# SUBBOARD-gate_driver.net
KiCad netlist of a schematic drawn in Altium Designer
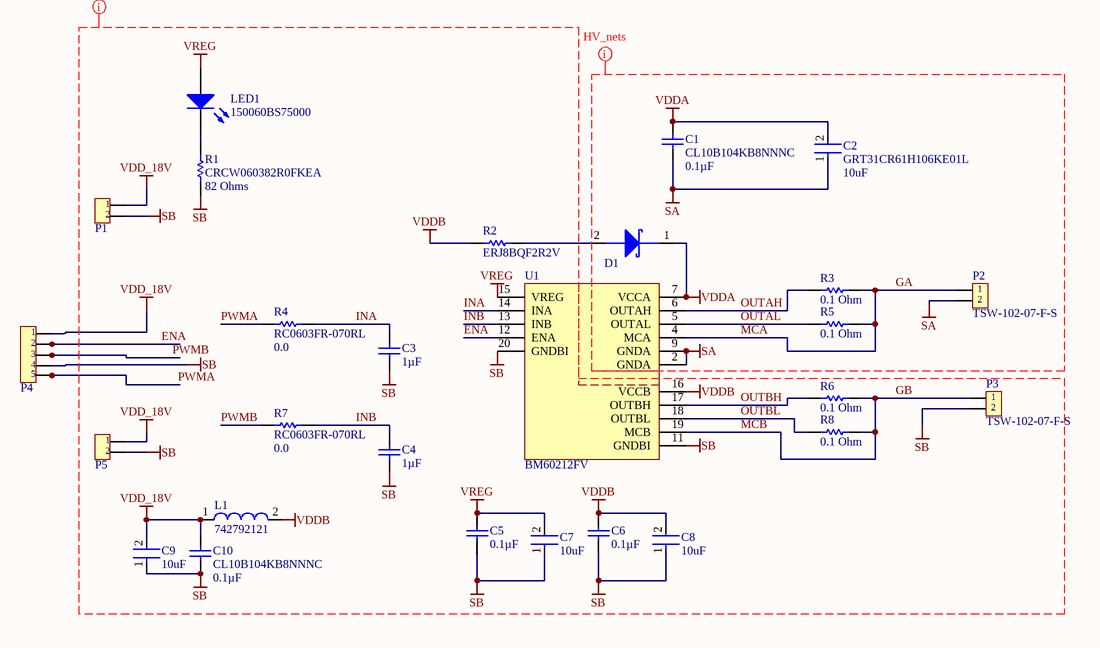
[diagram p0: SUBBOARD-gate_driver.SchDoc]

(export (version "E")
  (design (tool "Eeschema 10.0.6"))
  (components
    (comp (ref "C1")
      (value "CL10B104KB8NNNC")
      (footprint "SAMS-C0603-2_L")
      (description "Multi-layer Ceramic Capacitor, -55 to 125 degC, 2-Pin SMD (0603), RoHS, Tape and Reel")
      (fields (field (name "CAPACITANCE") "0.1µF") (field (name "MANUFACTURER") "Samsung Electro-Mechanics"))
      (libsource (lib "Altium Content Vault") (part "CAP-NP-2"))
    )
    (comp (ref "C2")
      (value "GRT31CR61H106KE01L")
      (footprint "FP-GRT31-0_2-MFG")
      (description "CAP CER 10UF 50V X5R 1206")
      (fields
        (field (name "TOLERANCE") "10%")
        (field (name "OCTOPART") "https://octopart.com/grt31cr61h106ke01l-murata-62921736")
        (field (name "ALTIUM_VALUE") "10uF")
      )
      (libsource (lib "Altium Content Vault") (part "11868f565c42a9108669ba33697ecf6"))
    )
    (comp (ref "C3")
      (value "LMK107B7105KA-T")
      (footprint "CAPC1608X90X35LL10T25")
      (fields
        (field (name "CAPACITANCE") "1µF")
        (field (name "TOLERANCE") "±10%")
        (field (name "MANUFACTURER") "Taiyo Yuden")
        (field (name "PCN PART NUMBER") "X5R,X7RDielectrics23/Jan/2008")
      )
      (libsource (lib "Altium Content Vault") (part "CAP-NP-2"))
    )
    (comp (ref "C4")
      (value "LMK107B7105KA-T")
      (footprint "CAPC1608X90X35LL10T25")
      (fields
        (field (name "CAPACITANCE") "1µF")
        (field (name "TOLERANCE") "±10%")
        (field (name "MANUFACTURER") "Taiyo Yuden")
        (field (name "PCN PART NUMBER") "X5R,X7RDielectrics23/Jan/2008")
      )
      (libsource (lib "Altium Content Vault") (part "CAP-NP-2"))
    )
    (comp (ref "C5")
      (value "CL10B104KB8NNNC")
      (footprint "SAMS-C0603-2_L")
      (description "Multi-layer Ceramic Capacitor, -55 to 125 degC, 2-Pin SMD (0603), RoHS, Tape and Reel")
      (fields (field (name "CAPACITANCE") "0.1µF") (field (name "MANUFACTURER") "Samsung Electro-Mechanics"))
      (libsource (lib "Altium Content Vault") (part "CAP-NP-2"))
    )
    (comp (ref "C6")
      (value "CL10B104KB8NNNC")
      (footprint "SAMS-C0603-2_L")
      (description "Multi-layer Ceramic Capacitor, -55 to 125 degC, 2-Pin SMD (0603), RoHS, Tape and Reel")
      (fields (field (name "CAPACITANCE") "0.1µF") (field (name "MANUFACTURER") "Samsung Electro-Mechanics"))
      (libsource (lib "Altium Content Vault") (part "CAP-NP-2"))
    )
    (comp (ref "C7")
      (value "10uF")
      (footprint "FP-GRT31-0_2-MFG")
      (description "CAP CER 10UF 50V X5R 1206")
      (fields
        (field (name "TOLERANCE") "10%")
        (field (name "OCTOPART") "https://octopart.com/grt31cr61h106ke01l-murata-62921736")
      )
      (libsource (lib "Altium Content Vault") (part "11868f565c42a9108669ba33697ecf6"))
    )
    (comp (ref "C8")
      (value "10uF")
      (footprint "FP-GRT31-0_2-MFG")
      (description "CAP CER 10UF 50V X5R 1206")
      (fields
        (field (name "TOLERANCE") "10%")
        (field (name "OCTOPART") "https://octopart.com/grt31cr61h106ke01l-murata-62921736")
      )
      (libsource (lib "Altium Content Vault") (part "11868f565c42a9108669ba33697ecf6"))
    )
    (comp (ref "C9")
      (value "10uF")
      (footprint "FP-GRT31-0_2-MFG")
      (description "CAP CER 10UF 50V X5R 1206")
      (fields
        (field (name "TOLERANCE") "10%")
        (field (name "OCTOPART") "https://octopart.com/grt31cr61h106ke01l-murata-62921736")
      )
      (libsource (lib "Altium Content Vault") (part "11868f565c42a9108669ba33697ecf6"))
    )
    (comp (ref "C10")
      (value "CL10B104KB8NNNC")
      (footprint "SAMS-C0603-2_L")
      (description "Multi-layer Ceramic Capacitor, -55 to 125 degC, 2-Pin SMD (0603), RoHS, Tape and Reel")
      (fields (field (name "CAPACITANCE") "0.1µF") (field (name "MANUFACTURER") "Samsung Electro-Mechanics"))
      (libsource (lib "Altium Content Vault") (part "CAP-NP-2"))
    )
    (comp (ref "D1")
      (value "BYG23T-M3/TR")
      (footprint "BYG23T-M3/TR")
      (description "DIODE AVALANCHE 1300V 1A DO214AC")
      (fields (field (name "MANUFACTURER") "Vishay Semiconductors"))
      (libsource (lib "Altium_Library_POWERLAB") (part "BYG23T-M3/TR"))
    )
    (comp (ref "L1")
      (value "742792121")
      (footprint "SMD-1206")
      (description "SMD EMI Suppression Ferrite Bead WE-CBF, Z = 300 Ohm")
      (libsource (lib "Altium Content Vault") (part "PAS-IND-INDUCTOR-2"))
    )
    (comp (ref "LED1")
      (value "150060BS75000")
      (footprint "0603_A")
      (description "SMD mono-color Chip LED, WL-SMCW, Blue")
      (fields (field (name "MANUFACTURER") "Wuerth Elektronik"))
      (libsource (lib "Altium Content Vault") (part "WE-LED_K1A2-2"))
    )
    (comp (ref "P1")
      (value "TSW-102-05-G-S")
      (footprint "TSW-102-05-G-S")
      (description "Conn Unshrouded Header HDR 2 POS 2.54mm Solder ST Thru-Hole Automotive Bulk")
      (fields (field (name "MANUFACTURER") "Samtec"))
      (libsource (lib "Altium_Library_POWERLAB") (part "TSW-102-05-G-S"))
    )
    (comp (ref "P2")
      (value "TSW-102-07-F-S")
      (footprint "TSW-102-07-F-S")
      (description "Conn Unshrouded Header HDR 2 POS 2.54mm Solder ST Thru-Hole")
      (fields (field (name "MANUFACTURER") "Samtec"))
      (libsource (lib "Altium_Library_POWERLAB") (part "TSW-102-07-F-S"))
    )
    (comp (ref "P3")
      (value "TSW-102-07-F-S")
      (footprint "TSW-102-07-F-S")
      (description "Conn Unshrouded Header HDR 2 POS 2.54mm Solder ST Thru-Hole")
      (fields (field (name "MANUFACTURER") "Samtec"))
      (libsource (lib "Altium_Library_POWERLAB") (part "TSW-102-07-F-S"))
    )
    (comp (ref "P4")
      (value "TSW-105-07-G-S")
      (footprint "TSW-105-07-G-S")
      (fields (field (name "MANUFACTURER") "Samtec"))
      (libsource (lib "Altium_Library_POWERLAB") (part "TSW-105-07-G-S"))
    )
    (comp (ref "P5")
      (value "TSW-102-05-G-S")
      (footprint "TSW-102-05-G-S")
      (description "Conn Unshrouded Header HDR 2 POS 2.54mm Solder ST Thru-Hole Automotive Bulk")
      (fields (field (name "MANUFACTURER") "Samtec"))
      (libsource (lib "Altium_Library_POWERLAB") (part "TSW-102-05-G-S"))
    )
    (comp (ref "R1")
      (value "CRCW060382R0FKEA")
      (footprint "RESC1609X50X30LL10T20")
      (fields (field (name "MANUFACTURER") "Vishay Dale") (field (name "ALTIUM_VALUE") "82 Ohms"))
      (libsource (lib "Altium Content Vault") (part "RES"))
    )
    (comp (ref "R2")
      (value "ERJ8BQF2R2V")
      (footprint "RESC3216X70X50NL05T20")
      (fields (field (name "MANUFACTURER") "Panasonic"))
      (libsource (lib "Altium Content Vault") (part "RES"))
    )
    (comp (ref "R3")
      (value "0.1 Ohm")
      (footprint "RESC3216X70X50LL05T20")
      (fields (field (name "MANUFACTURER") "Panasonic") (field (name "PART NUMBER") "ERJ8BWFR100V"))
      (libsource (lib "Altium Content Vault") (part "RES"))
    )
    (comp (ref "R4")
      (value "RC0603FR-070RL")
      (footprint "RESC1608X55X25LL10T15")
      (description "Chip Resistor, 0 Ohm, +/- 1%, 100 mW, -55 to 155 degC, 0603 (1608 Metric), RoHS, Tape and Reel")
      (fields
        (field (name "RESISTANCE (OHMS)") "0.0")
        (field (name "MANUFACTURER") "Yageo")
        (field (name "TOLERANCE") "Jumper")
      )
      (libsource (lib "Altium Content Vault") (part "RES-2"))
    )
    (comp (ref "R5")
      (value "0.1 Ohm")
      (footprint "RESC3216X70X50LL05T20")
      (fields (field (name "MANUFACTURER") "Panasonic") (field (name "PART NUMBER") "ERJ8BWFR100V"))
      (libsource (lib "Altium Content Vault") (part "RES"))
    )
    (comp (ref "R6")
      (value "0.1 Ohm")
      (footprint "RESC3216X70X50LL05T20")
      (fields (field (name "MANUFACTURER") "Panasonic") (field (name "PART NUMBER") "ERJ8BWFR100V"))
      (libsource (lib "Altium Content Vault") (part "RES"))
    )
    (comp (ref "R7")
      (value "RC0603FR-070RL")
      (footprint "RESC1608X55X25LL10T15")
      (description "Chip Resistor, 0 Ohm, +/- 1%, 100 mW, -55 to 155 degC, 0603 (1608 Metric), RoHS, Tape and Reel")
      (fields
        (field (name "RESISTANCE (OHMS)") "0.0")
        (field (name "MANUFACTURER") "Yageo")
        (field (name "TOLERANCE") "Jumper")
      )
      (libsource (lib "Altium Content Vault") (part "RES-2"))
    )
    (comp (ref "R8")
      (value "0.1 Ohm")
      (footprint "RESC3216X70X50LL05T20")
      (fields (field (name "MANUFACTURER") "Panasonic") (field (name "PART NUMBER") "ERJ8BWFR100V"))
      (libsource (lib "Altium Content Vault") (part "RES"))
    )
    (comp (ref "U1")
      (value "BM60212FV")
      (footprint "SOP65P810X190-20N")
      (description "MOSFET and Power Driver 2-OUT Hi/Lo Side Non-Inv 20-Pin SSOP-BW Emboss T/R")
      (fields (field (name "MANUFACTURER") "Rohm") (field (name "MANUFACTURER PART NUMBER") "BM60212FV-CE2"))
      (libsource (lib "Altium_Library_POWERLAB") (part "BM60212FV-CE2"))
    )
  )
  (nets
    (net (code "1") (name "/ENA") (class "Default")
      (node (ref "P4") (pin "2") (pinfunction "2_2") (pintype "passive"))
      (node (ref "U1") (pin "12") (pinfunction "ENA_12") (pintype "passive"))
    )
    (net (code "2") (name "/GA") (class "Default")
      (node (ref "P2") (pin "1") (pinfunction "1_1") (pintype "passive"))
      (node (ref "R3") (pin "1") (pinfunction "1_1") (pintype "passive"))
      (node (ref "R5") (pin "1") (pinfunction "1_1") (pintype "passive"))
      (node (ref "U1") (pin "4") (pinfunction "MCA_4") (pintype "passive"))
    )
    (net (code "3") (name "/GB") (class "Default")
      (node (ref "P3") (pin "1") (pinfunction "1_1") (pintype "passive"))
      (node (ref "R6") (pin "1") (pinfunction "1_1") (pintype "passive"))
      (node (ref "R8") (pin "1") (pinfunction "1_1") (pintype "passive"))
      (node (ref "U1") (pin "19") (pinfunction "MCB_19") (pintype "passive"))
    )
    (net (code "4") (name "/INA") (class "Default")
      (node (ref "C3") (pin "1") (pinfunction "1_1") (pintype "passive"))
      (node (ref "R4") (pin "1") (pinfunction "1_1") (pintype "passive"))
      (node (ref "U1") (pin "14") (pinfunction "INA_14") (pintype "passive"))
    )
    (net (code "5") (name "/INB") (class "Default")
      (node (ref "C4") (pin "1") (pinfunction "1_1") (pintype "passive"))
      (node (ref "R7") (pin "1") (pinfunction "1_1") (pintype "passive"))
      (node (ref "U1") (pin "13") (pinfunction "INB_13") (pintype "passive"))
    )
    (net (code "6") (name "/OUTAH") (class "Default")
      (node (ref "R3") (pin "2") (pinfunction "2_2") (pintype "passive"))
      (node (ref "U1") (pin "6") (pinfunction "OUTAH_6") (pintype "passive"))
    )
    (net (code "7") (name "/OUTAL") (class "Default")
      (node (ref "R5") (pin "2") (pinfunction "2_2") (pintype "passive"))
      (node (ref "U1") (pin "5") (pinfunction "OUTAL_5") (pintype "passive"))
    )
    (net (code "8") (name "/OUTBH") (class "Default")
      (node (ref "R6") (pin "2") (pinfunction "2_2") (pintype "passive"))
      (node (ref "U1") (pin "17") (pinfunction "OUTBH_17") (pintype "passive"))
    )
    (net (code "9") (name "/OUTBL") (class "Default")
      (node (ref "R8") (pin "2") (pinfunction "2_2") (pintype "passive"))
      (node (ref "U1") (pin "18") (pinfunction "OUTBL_18") (pintype "passive"))
    )
    (net (code "10") (name "/PWMA") (class "Default")
      (node (ref "P4") (pin "5") (pinfunction "5_5") (pintype "passive"))
      (node (ref "R4") (pin "2") (pinfunction "2_2") (pintype "passive"))
    )
    (net (code "11") (name "/PWMB") (class "Default")
      (node (ref "P4") (pin "3") (pinfunction "3_3") (pintype "passive"))
      (node (ref "R7") (pin "2") (pinfunction "2_2") (pintype "passive"))
    )
    (net (code "12") (name "Net-(D1-Anode)") (class "Default")
      (node (ref "D1") (pin "2") (pinfunction "Anode_2") (pintype "passive"))
      (node (ref "R2") (pin "2") (pinfunction "2_2") (pintype "passive"))
    )
    (net (code "13") (name "Net-(LED1-K)") (class "Default")
      (node (ref "LED1") (pin "1") (pinfunction "K_1") (pintype "passive"))
      (node (ref "R1") (pin "1") (pinfunction "1_1") (pintype "passive"))
    )
    (net (code "14") (name "SA") (class "Default")
      (node (ref "C1") (pin "2") (pinfunction "2_2") (pintype "passive"))
      (node (ref "C2") (pin "1") (pinfunction "1_1") (pintype "passive"))
      (node (ref "P2") (pin "2") (pinfunction "2_2") (pintype "passive"))
      (node (ref "U1") (pin "2") (pinfunction "GNDA_2") (pintype "passive"))
      (node (ref "U1") (pin "9") (pinfunction "GNDA_9") (pintype "passive"))
    )
    (net (code "15") (name "SB") (class "Default")
      (node (ref "C10") (pin "2") (pinfunction "2_2") (pintype "passive"))
      (node (ref "C3") (pin "2") (pinfunction "2_2") (pintype "passive"))
      (node (ref "C4") (pin "2") (pinfunction "2_2") (pintype "passive"))
      (node (ref "C5") (pin "2") (pinfunction "2_2") (pintype "passive"))
      (node (ref "C6") (pin "2") (pinfunction "2_2") (pintype "passive"))
      (node (ref "C7") (pin "1") (pinfunction "1_1") (pintype "passive"))
      (node (ref "C8") (pin "1") (pinfunction "1_1") (pintype "passive"))
      (node (ref "C9") (pin "1") (pinfunction "1_1") (pintype "passive"))
      (node (ref "P1") (pin "2") (pinfunction "2_2") (pintype "passive"))
      (node (ref "P3") (pin "2") (pinfunction "2_2") (pintype "passive"))
      (node (ref "P4") (pin "4") (pinfunction "4_4") (pintype "passive"))
      (node (ref "P5") (pin "2") (pinfunction "2_2") (pintype "passive"))
      (node (ref "R1") (pin "2") (pinfunction "2_2") (pintype "passive"))
      (node (ref "U1") (pin "11") (pinfunction "GNDBI_11") (pintype "passive"))
      (node (ref "U1") (pin "20") (pinfunction "GNDBI_20") (pintype "passive"))
    )
    (net (code "16") (name "VDDA") (class "Default")
      (node (ref "C1") (pin "1") (pinfunction "1_1") (pintype "passive"))
      (node (ref "C2") (pin "2") (pinfunction "2_2") (pintype "passive"))
      (node (ref "D1") (pin "1") (pinfunction "Cathode_1") (pintype "passive"))
      (node (ref "U1") (pin "7") (pinfunction "VCCA_7") (pintype "passive"))
    )
    (net (code "17") (name "VDDB") (class "Default")
      (node (ref "C6") (pin "1") (pinfunction "1_1") (pintype "passive"))
      (node (ref "C8") (pin "2") (pinfunction "2_2") (pintype "passive"))
      (node (ref "L1") (pin "2") (pinfunction "2_2") (pintype "passive"))
      (node (ref "R2") (pin "1") (pinfunction "1_1") (pintype "passive"))
      (node (ref "U1") (pin "16") (pinfunction "VCCB_16") (pintype "passive"))
    )
    (net (code "18") (name "VDD_18V") (class "Default")
      (node (ref "C10") (pin "1") (pinfunction "1_1") (pintype "passive"))
      (node (ref "C9") (pin "2") (pinfunction "2_2") (pintype "passive"))
      (node (ref "L1") (pin "1") (pinfunction "1_1") (pintype "passive"))
      (node (ref "P1") (pin "1") (pinfunction "1_1") (pintype "passive"))
      (node (ref "P4") (pin "1") (pinfunction "1_1") (pintype "passive"))
      (node (ref "P5") (pin "1") (pinfunction "1_1") (pintype "passive"))
    )
    (net (code "19") (name "VREG") (class "Default")
      (node (ref "C5") (pin "1") (pinfunction "1_1") (pintype "passive"))
      (node (ref "C7") (pin "2") (pinfunction "2_2") (pintype "passive"))
      (node (ref "LED1") (pin "2") (pinfunction "A_2") (pintype "passive"))
      (node (ref "U1") (pin "15") (pinfunction "VREG_15") (pintype "passive"))
    )
  )
)
